# 3.net
KiCad netlist of a schematic drawn in Altium Designer
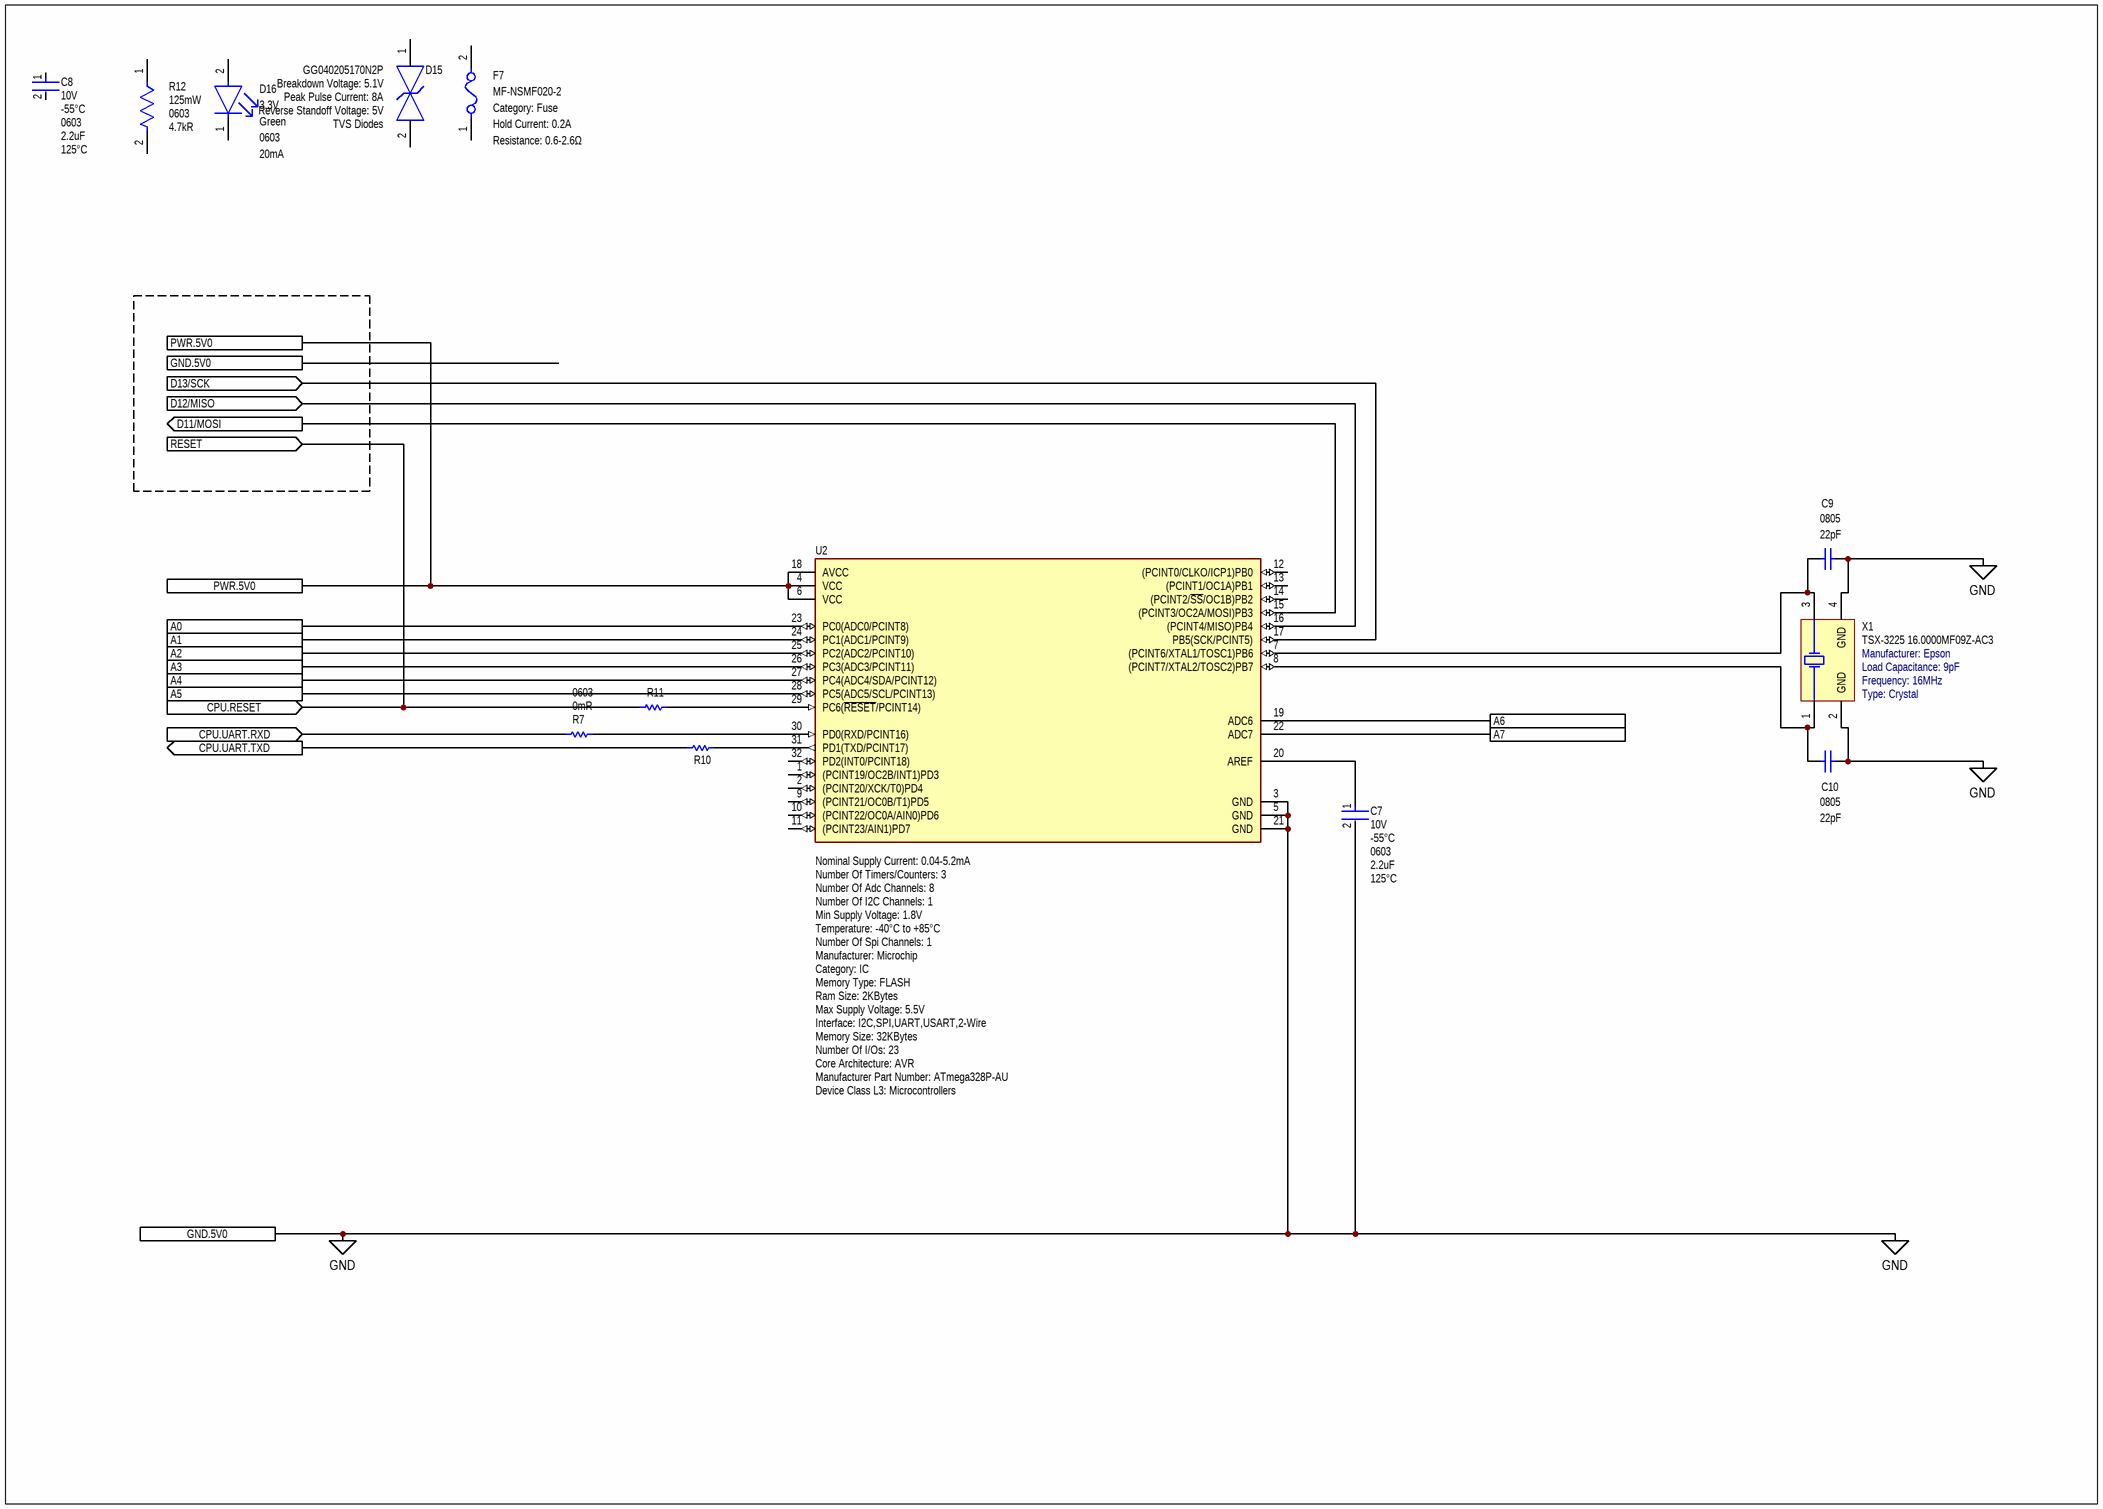
[diagram p0: Блок3.SchDoc]

(export (version "E")
  (design (tool "Eeschema 10.0.6"))
  (components
    (comp (ref "C7")
      (value "CL10B225KP8NFNC")
      (footprint "FP-CL10-IPC_A")
      (description "Cap Ceramic 2.2uF 10V X7R ±10% Pad SMD 0603 +125°C T/R")
      (fields
        (field (name "VOLTAGE RATING") "10V")
        (field (name "MIN OPERATING TEMPERATURE") "-55°C")
        (field (name "CASE CODE (IMPERIAL)") "0603")
        (field (name "CAPACITANCE") "2.2uF")
        (field (name "MAX OPERATING TEMPERATURE") "125°C")
        (field (name "TOLERANCE") "10%")
      )
      (libsource (lib "Altium Content Vault") (part "b4654b650e69147ec39a6b967a45e02"))
    )
    (comp (ref "C8")
      (value "CL10B225KP8NFNC")
      (footprint "FP-CL10-IPC_A")
      (description "Cap Ceramic 2.2uF 10V X7R ±10% Pad SMD 0603 +125°C T/R")
      (fields
        (field (name "VOLTAGE RATING") "10V")
        (field (name "MIN OPERATING TEMPERATURE") "-55°C")
        (field (name "CASE CODE (IMPERIAL)") "0603")
        (field (name "CAPACITANCE") "2.2uF")
        (field (name "MAX OPERATING TEMPERATURE") "125°C")
        (field (name "TOLERANCE") "10%")
      )
      (libsource (lib "Altium Content Vault") (part "b4654b650e69147ec39a6b967a45e02"))
    )
    (comp (ref "C9")
      (value "VJ0805A220GXXCW1BC")
      (footprint "CAPC2013X145X50ML20T20")
      (fields
        (field (name "MANUFACTURER") "Vitramon")
        (field (name "CASE/PACKAGE") "0805")
        (field (name "CAPACITANCE") "22pF")
        (field (name "TOLERANCE") "2%")
      )
      (libsource (lib "Altium Content Vault") (part "CAP"))
    )
    (comp (ref "C10")
      (value "VJ0805A220GXXCW1BC")
      (footprint "CAPC2013X145X50ML20T20")
      (fields
        (field (name "MANUFACTURER") "Vitramon")
        (field (name "CASE/PACKAGE") "0805")
        (field (name "CAPACITANCE") "22pF")
        (field (name "TOLERANCE") "2%")
      )
      (libsource (lib "Altium Content Vault") (part "CAP"))
    )
    (comp (ref "D15")
      (value "GG040205170N2P")
      (footprint "FP-GG0402-IPC_A")
      (description "TVS DIODE 5V 10V 0402")
      (fields
        (field (name "OCTOPART") "https://octopart.com/gg040205170n2p-avx-81066082")
        (field (name "MANUFACTURER") "AVX")
        (field (name "BREAKDOWN VOLTAGE") "5.1V")
        (field (name "PEAK PULSE CURRENT") "8A")
        (field (name "REVERSE STANDOFF VOLTAGE") "5V")
        (field (name "DEVICE CLASS L2") "TVS Diodes")
      )
      (libsource (lib "Altium Content Vault") (part "11bd9d59d340f0612179daf16ad9b72"))
    )
    (comp (ref "D16")
      (value "APT1608ZGCK")
      (footprint "FP-APT1608ZGCK-MFG")
      (description "LED GREEN CLEAR CHIP SMD")
      (fields
        (field (name "FORWARD VOLTAGE") "3.3V")
        (field (name "COLOR") "Green")
        (field (name "CASE/PACKAGE") "0603")
        (field (name "FORWARD CURRENT") "20mA")
      )
      (libsource (lib "Altium Content Vault") (part "8706943c75ba83719d021d2fdc84c58"))
    )
    (comp (ref "F7")
      (value "MF-NSMF020-2")
      (footprint "FP-MF-NSMF020-2-MFG")
      (description "PTC RESET FUSE 24V 200MA 1206")
      (fields
        (field (name "CATEGORY") "Fuse")
        (field (name "HOLD CURRENT") "0.2A")
        (field (name "MANUFACTURER") "Bourns")
        (field (name "OCTOPART") "https://octopart.com/mf-nsmf020-2-bourns-94649")
        (field (name "RESISTANCE") "0.6-2.6Ω")
      )
      (libsource (lib "Altium Content Vault") (part "5bcf9b9f640e542cf0359d10258e979"))
    )
    (comp (ref "R7")
      (value "CRCW06030000Z0EA")
      (footprint "RESC1609X50X30NL8T20")
      (description "Chip Resistor, 0 Ohm, Jumper, 100 mW, -55 to 155 degC, 0603 (1608 Metric), RoHS, Tape and Reel")
      (fields
        (field (name "MANUFACTURER") "Vishay")
        (field (name "PACKAGEREFERENCE") "0603")
        (field (name "MANUFACTURER PART NUMBER") "CRCW0603-0000Z0EA")
        (field (name "RESISTANCE") "0mR")
      )
      (libsource (lib "Altium Content Vault") (part "RES-2"))
    )
    (comp (ref "R10")
      (value "CRCW06030000Z0EA")
      (footprint "RESC1609X50X30NL8T20")
      (description "Chip Resistor, 0 Ohm, Jumper, 100 mW, -55 to 155 degC, 0603 (1608 Metric), RoHS, Tape and Reel")
      (fields
        (field (name "MANUFACTURER") "Vishay")
        (field (name "MANUFACTURER PART NUMBER") "CRCW0603-0000Z0EA")
      )
      (libsource (lib "Altium Content Vault") (part "RES-2"))
    )
    (comp (ref "R11")
      (value "CRCW06030000Z0EA")
      (footprint "RESC1609X50X30NL8T20")
      (description "Chip Resistor, 0 Ohm, Jumper, 100 mW, -55 to 155 degC, 0603 (1608 Metric), RoHS, Tape and Reel")
      (fields
        (field (name "MANUFACTURER") "Vishay")
        (field (name "MANUFACTURER PART NUMBER") "CRCW0603-0000Z0EA")
      )
      (libsource (lib "Altium Content Vault") (part "RES-2"))
    )
    (comp (ref "R12")
      (value "MCT06030C4701FP500")
      (footprint "FP-MCT0603-MFG")
      (description "RES SMD 100 OHM 1% 1/8W 0603")
      (fields
        (field (name "POWER RATING") "125mW")
        (field (name "CASE/PACKAGE") "0603")
        (field (name "RESISTANCE") "4.7kR")
        (field (name "TOLERANCE") "1%")
      )
      (libsource (lib "Altium Content Vault") (part "1029c3af85768c4190bb7ad29bc67b5"))
    )
    (comp (ref "U2")
      (value "ATmega328P-AU")
      (footprint "FP-32A-IPC_A")
      (description "IC MCU 8BIT 32KB FLASH 32TQFP")
      (fields
        (field (name "NOMINAL SUPPLY CURRENT") "0.04-5.2mA")
        (field (name "NUMBER OF TIMERS/COUNTERS") "3")
        (field (name "NUMBER OF ADC CHANNELS") "8")
        (field (name "NUMBER OF I2C CHANNELS") "1")
        (field (name "MIN SUPPLY VOLTAGE") "1.8V")
        (field (name "TEMPERATURE") "-40°C to +85°C")
        (field (name "NUMBER OF SPI CHANNELS") "1")
        (field (name "MANUFACTURER") "Microchip")
        (field (name "CATEGORY") "IC")
        (field (name "MEMORY TYPE") "FLASH")
        (field (name "OCTOPART") "https://octopart.com/atmega328p-au-microchip-77760215")
        (field (name "RAM SIZE") "2KBytes")
        (field (name "MAX SUPPLY VOLTAGE") "5.5V")
        (field (name "INTERFACE") "I2C,SPI,UART,USART,2-Wire")
        (field (name "MEMORY SIZE") "32KBytes")
        (field (name "NUMBER OF I/OS") "23")
        (field (name "CORE ARCHITECTURE") "AVR")
        (field (name "MANUFACTURER PART NUMBER") "ATmega328P-AU")
        (field (name "DEVICE CLASS L3") "Microcontrollers")
      )
      (libsource (lib "Altium Content Vault") (part "f5fbdcb2c0c597ef7d3dd1575aef21a"))
    )
    (comp (ref "X1")
      (value "TSX-3225 16.0000MF09Z-AC3")
      (footprint "EPSON-TSX-3225_V")
      (description "Crystal, 16 MHz, -40 to 85 degC, 4-Pin SMD, RoHS, Tape and Reel")
      (fields
        (field (name "MANUFACTURER") "Epson")
        (field (name "LOAD CAPACITANCE") "9pF")
        (field (name "FREQUENCY") "16MHz")
        (field (name "TYPE") "Crystal")
        (field (name "TOLERANCE") "10PPM")
      )
      (libsource (lib "Altium Content Vault") (part "XTAL-1-3-4"))
    )
  )
  (nets
    (net (code "1") (name "/A0") (class "Default")
      (node (ref "U2") (pin "23") (pinfunction "PC0(ADC0/PCINT8)_23") (pintype "bidirectional"))
    )
    (net (code "2") (name "/A1") (class "Default")
      (node (ref "U2") (pin "24") (pinfunction "PC1(ADC1/PCINT9)_24") (pintype "bidirectional"))
    )
    (net (code "3") (name "/A2") (class "Default")
      (node (ref "U2") (pin "25") (pinfunction "PC2(ADC2/PCINT10)_25") (pintype "bidirectional"))
    )
    (net (code "4") (name "/A3") (class "Default")
      (node (ref "U2") (pin "26") (pinfunction "PC3(ADC3/PCINT11)_26") (pintype "bidirectional"))
    )
    (net (code "5") (name "/A4") (class "Default")
      (node (ref "U2") (pin "27") (pinfunction "PC4(ADC4/SDA/PCINT12)_27") (pintype "bidirectional"))
    )
    (net (code "6") (name "/A5") (class "Default")
      (node (ref "U2") (pin "28") (pinfunction "PC5(ADC5/SCL/PCINT13)_28") (pintype "bidirectional"))
    )
    (net (code "7") (name "/A6") (class "Default")
      (node (ref "U2") (pin "19") (pinfunction "ADC6_19") (pintype "power_in"))
    )
    (net (code "8") (name "/A7") (class "Default")
      (node (ref "U2") (pin "22") (pinfunction "ADC7_22") (pintype "passive"))
    )
    (net (code "9") (name "/CPU.RESET") (class "Default")
      (node (ref "R11") (pin "1") (pinfunction "1_1") (pintype "passive"))
    )
    (net (code "10") (name "/CPU.UART.RXD") (class "Default")
      (node (ref "R7") (pin "1") (pinfunction "1_1") (pintype "passive"))
    )
    (net (code "11") (name "/CPU.UART.TXD") (class "Default")
      (node (ref "R10") (pin "1") (pinfunction "1_1") (pintype "passive"))
    )
    (net (code "12") (name "/D11{slash}MOSI") (class "Default")
      (node (ref "U2") (pin "15") (pinfunction "(PCINT3/OC2A/MOSI)PB3_15") (pintype "bidirectional"))
    )
    (net (code "13") (name "/D12{slash}MISO") (class "Default")
      (node (ref "U2") (pin "16") (pinfunction "(PCINT4/MISO)PB4_16") (pintype "bidirectional"))
    )
    (net (code "14") (name "/D13{slash}SCK") (class "Default")
      (node (ref "U2") (pin "17") (pinfunction "PB5(SCK/PCINT5)_17") (pintype "bidirectional"))
    )
    (net (code "15") (name "/PWR.5V0") (class "Default")
      (node (ref "U2") (pin "18") (pinfunction "AVCC_18") (pintype "power_in"))
      (node (ref "U2") (pin "4") (pinfunction "VCC_4") (pintype "power_in"))
      (node (ref "U2") (pin "6") (pinfunction "VCC_6") (pintype "power_in"))
    )
    (net (code "16") (name "GND") (class "Default")
      (node (ref "C10") (pin "2") (pinfunction "2_2") (pintype "passive"))
      (node (ref "C7") (pin "2") (pinfunction "2_2") (pintype "passive"))
      (node (ref "C9") (pin "2") (pinfunction "2_2") (pintype "passive"))
      (node (ref "U2") (pin "21") (pinfunction "GND_21") (pintype "power_in"))
      (node (ref "U2") (pin "3") (pinfunction "GND_3") (pintype "power_in"))
      (node (ref "U2") (pin "5") (pinfunction "GND_5") (pintype "power_in"))
      (node (ref "X1") (pin "2") (pinfunction "GND_2") (pintype "power_in"))
      (node (ref "X1") (pin "4") (pinfunction "GND_4") (pintype "power_in"))
    )
    (net (code "17") (name "Net-(U2-(PCINT6{slash}XTAL1{slash}TOSC1)PB6)") (class "Default")
      (node (ref "C9") (pin "1") (pinfunction "1_1") (pintype "passive"))
      (node (ref "U2") (pin "7") (pinfunction "(PCINT6/XTAL1/TOSC1)PB6_7") (pintype "bidirectional"))
      (node (ref "X1") (pin "3") (pinfunction "X2_3") (pintype "passive"))
    )
    (net (code "18") (name "Net-(U2-(PCINT7{slash}XTAL2{slash}TOSC2)PB7)") (class "Default")
      (node (ref "C10") (pin "1") (pinfunction "1_1") (pintype "passive"))
      (node (ref "U2") (pin "8") (pinfunction "(PCINT7/XTAL2/TOSC2)PB7_8") (pintype "bidirectional"))
      (node (ref "X1") (pin "1") (pinfunction "X1_1") (pintype "passive"))
    )
    (net (code "19") (name "Net-(U2-AREF)") (class "Default")
      (node (ref "C7") (pin "1") (pinfunction "1_1") (pintype "passive"))
      (node (ref "U2") (pin "20") (pinfunction "AREF_20") (pintype "passive"))
    )
    (net (code "20") (name "Net-(U2-PC6(~{RESET}{slash}PCINT14))") (class "Default")
      (node (ref "R11") (pin "2") (pinfunction "2_2") (pintype "passive"))
      (node (ref "U2") (pin "29") (pinfunction "PC6(~{RESET}/PCINT14)_29") (pintype "input"))
    )
    (net (code "21") (name "Net-(U2-PD0(RXD{slash}PCINT16))") (class "Default")
      (node (ref "R7") (pin "2") (pinfunction "2_2") (pintype "passive"))
      (node (ref "U2") (pin "30") (pinfunction "PD0(RXD/PCINT16)_30") (pintype "input"))
    )
    (net (code "22") (name "Net-(U2-PD1(TXD{slash}PCINT17))") (class "Default")
      (node (ref "R10") (pin "2") (pinfunction "2_2") (pintype "passive"))
      (node (ref "U2") (pin "31") (pinfunction "PD1(TXD/PCINT17)_31") (pintype "output"))
    )
    (net (code "23") (name "unconnected-(C8-Pad1)") (class "Default")
      (node (ref "C8") (pin "1") (pinfunction "1_1") (pintype "passive"))
    )
    (net (code "24") (name "unconnected-(C8-Pad2)") (class "Default")
      (node (ref "C8") (pin "2") (pinfunction "2_2") (pintype "passive"))
    )
    (net (code "25") (name "unconnected-(D15-Pad1)") (class "Default")
      (node (ref "D15") (pin "1") (pinfunction "1_1") (pintype "passive"))
    )
    (net (code "26") (name "unconnected-(D15-Pad2)") (class "Default")
      (node (ref "D15") (pin "2") (pinfunction "2_2") (pintype "passive"))
    )
    (net (code "27") (name "unconnected-(D16-A-Pad2)") (class "Default")
      (node (ref "D16") (pin "2") (pinfunction "A_2") (pintype "passive"))
    )
    (net (code "28") (name "unconnected-(D16-C-Pad1)") (class "Default")
      (node (ref "D16") (pin "1") (pinfunction "C_1") (pintype "passive"))
    )
    (net (code "29") (name "unconnected-(F7-Pad1)") (class "Default")
      (node (ref "F7") (pin "1") (pinfunction "1_1") (pintype "passive"))
    )
    (net (code "30") (name "unconnected-(F7-Pad2)") (class "Default")
      (node (ref "F7") (pin "2") (pinfunction "2_2") (pintype "passive"))
    )
    (net (code "31") (name "unconnected-(R12-Pad1)") (class "Default")
      (node (ref "R12") (pin "1") (pinfunction "1_1") (pintype "passive"))
    )
    (net (code "32") (name "unconnected-(R12-Pad2)") (class "Default")
      (node (ref "R12") (pin "2") (pinfunction "2_2") (pintype "passive"))
    )
    (net (code "33") (name "unconnected-(U2-(PCINT0{slash}CLKO{slash}ICP1)PB0-Pad12)") (class "Default")
      (node (ref "U2") (pin "12") (pinfunction "(PCINT0/CLKO/ICP1)PB0_12") (pintype "bidirectional"))
    )
    (net (code "34") (name "unconnected-(U2-(PCINT1{slash}OC1A)PB1-Pad13)") (class "Default")
      (node (ref "U2") (pin "13") (pinfunction "(PCINT1/OC1A)PB1_13") (pintype "bidirectional"))
    )
    (net (code "35") (name "unconnected-(U2-(PCINT2{slash}~{SS}{slash}OC1B)PB2-Pad14)") (class "Default")
      (node (ref "U2") (pin "14") (pinfunction "(PCINT2/~{SS}/OC1B)PB2_14") (pintype "bidirectional"))
    )
    (net (code "36") (name "unconnected-(U2-(PCINT19{slash}OC2B{slash}INT1)PD3-Pad1)") (class "Default")
      (node (ref "U2") (pin "1") (pinfunction "(PCINT19/OC2B/INT1)PD3_1") (pintype "bidirectional"))
    )
    (net (code "37") (name "unconnected-(U2-(PCINT20{slash}XCK{slash}T0)PD4-Pad2)") (class "Default")
      (node (ref "U2") (pin "2") (pinfunction "(PCINT20/XCK/T0)PD4_2") (pintype "bidirectional"))
    )
    (net (code "38") (name "unconnected-(U2-(PCINT21{slash}OC0B{slash}T1)PD5-Pad9)") (class "Default")
      (node (ref "U2") (pin "9") (pinfunction "(PCINT21/OC0B/T1)PD5_9") (pintype "bidirectional"))
    )
    (net (code "39") (name "unconnected-(U2-(PCINT22{slash}OC0A{slash}AIN0)PD6-Pad10)") (class "Default")
      (node (ref "U2") (pin "10") (pinfunction "(PCINT22/OC0A/AIN0)PD6_10") (pintype "bidirectional"))
    )
    (net (code "40") (name "unconnected-(U2-(PCINT23{slash}AIN1)PD7-Pad11)") (class "Default")
      (node (ref "U2") (pin "11") (pinfunction "(PCINT23/AIN1)PD7_11") (pintype "bidirectional"))
    )
    (net (code "41") (name "unconnected-(U2-PD2(INT0{slash}PCINT18)-Pad32)") (class "Default")
      (node (ref "U2") (pin "32") (pinfunction "PD2(INT0/PCINT18)_32") (pintype "bidirectional"))
    )
  )
)
